# LoRa_RX.net
KiCad netlist of a schematic drawn in Altium Designer
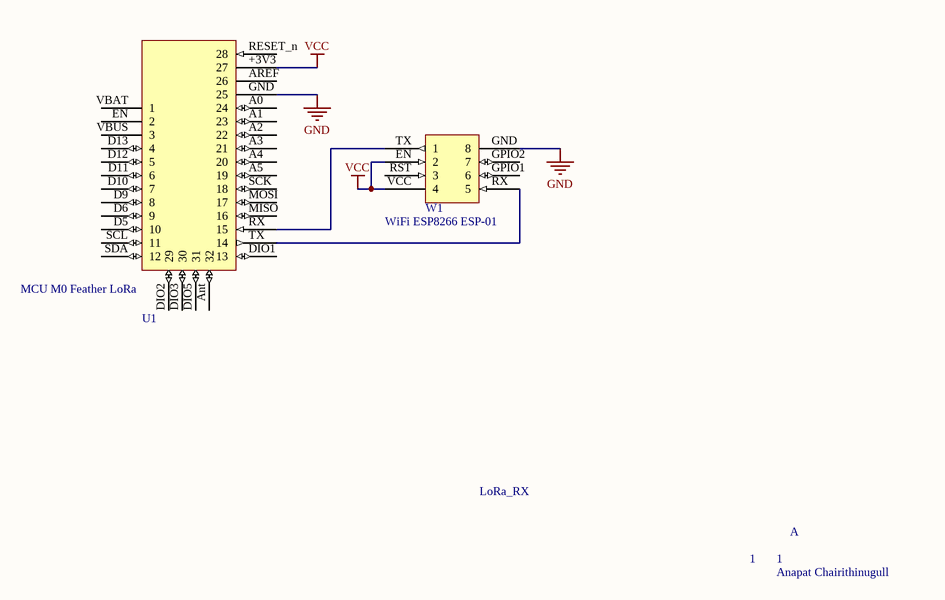
[diagram p0: LoRa_RX.SchDoc]

(export (version "E")
  (design (tool "Eeschema 10.0.6"))
  (components
    (comp (ref "U1") (value "MCU M0 Feather LoRa") (libsource (lib "Modules") (part "MCU M0 Feather LoRa")))
    (comp (ref "W1") (value "WiFi ESP8266 ESP-01") (libsource (lib "Modules") (part "WiFi ESP8266 ESP-01")))
  )
  (nets
    (net (code "1") (name "GND") (class "Default")
      (node (ref "U1") (pin "GND") (pinfunction "25_GND") (pintype "power_in"))
      (node (ref "W1") (pin "GND") (pinfunction "8_GND") (pintype "power_in"))
    )
    (net (code "2") (name "Net-(U1-14)") (class "Default")
      (node (ref "U1") (pin "TX") (pinfunction "14_TX") (pintype "output"))
      (node (ref "W1") (pin "RX") (pinfunction "5_RX") (pintype "input"))
    )
    (net (code "3") (name "Net-(U1-15)") (class "Default")
      (node (ref "U1") (pin "RX") (pinfunction "15_RX") (pintype "input"))
      (node (ref "W1") (pin "TX") (pinfunction "1_TX") (pintype "output"))
    )
    (net (code "4") (name "VCC") (class "Default")
      (node (ref "U1") (pin "+3V3") (pinfunction "27_+3V3") (pintype "power_in"))
      (node (ref "W1") (pin "EN") (pinfunction "2_EN") (pintype "input"))
      (node (ref "W1") (pin "VCC") (pinfunction "4_VCC") (pintype "power_in"))
    )
    (net (code "5") (name "unconnected-(U1-1-PadVBAT)") (class "Default")
      (node (ref "U1") (pin "VBAT") (pinfunction "1_VBAT") (pintype "power_in"))
    )
    (net (code "6") (name "unconnected-(U1-2-PadEN)") (class "Default")
      (node (ref "U1") (pin "EN") (pinfunction "2_EN") (pintype "power_in"))
    )
    (net (code "7") (name "unconnected-(U1-3-PadVBUS)") (class "Default")
      (node (ref "U1") (pin "VBUS") (pinfunction "3_VBUS") (pintype "power_in"))
    )
    (net (code "8") (name "unconnected-(U1-4-PadD13)") (class "Default")
      (node (ref "U1") (pin "D13") (pinfunction "4_D13") (pintype "bidirectional"))
    )
    (net (code "9") (name "unconnected-(U1-5-PadD12)") (class "Default")
      (node (ref "U1") (pin "D12") (pinfunction "5_D12") (pintype "bidirectional"))
    )
    (net (code "10") (name "unconnected-(U1-6-PadD11)") (class "Default")
      (node (ref "U1") (pin "D11") (pinfunction "6_D11") (pintype "bidirectional"))
    )
    (net (code "11") (name "unconnected-(U1-7-PadD10)") (class "Default")
      (node (ref "U1") (pin "D10") (pinfunction "7_D10") (pintype "bidirectional"))
    )
    (net (code "12") (name "unconnected-(U1-8-PadD9)") (class "Default")
      (node (ref "U1") (pin "D9") (pinfunction "8_D9") (pintype "bidirectional"))
    )
    (net (code "13") (name "unconnected-(U1-9-PadD6)") (class "Default")
      (node (ref "U1") (pin "D6") (pinfunction "9_D6") (pintype "bidirectional"))
    )
    (net (code "14") (name "unconnected-(U1-10-PadD5)") (class "Default")
      (node (ref "U1") (pin "D5") (pinfunction "10_D5") (pintype "bidirectional"))
    )
    (net (code "15") (name "unconnected-(U1-11-PadSCL)") (class "Default")
      (node (ref "U1") (pin "SCL") (pinfunction "11_SCL") (pintype "bidirectional"))
    )
    (net (code "16") (name "unconnected-(U1-12-PadSDA)") (class "Default")
      (node (ref "U1") (pin "SDA") (pinfunction "12_SDA") (pintype "bidirectional"))
    )
    (net (code "17") (name "unconnected-(U1-13-PadDIO1)") (class "Default")
      (node (ref "U1") (pin "DIO1") (pinfunction "13_DIO1") (pintype "bidirectional"))
    )
    (net (code "18") (name "unconnected-(U1-16-PadMISO)") (class "Default")
      (node (ref "U1") (pin "MISO") (pinfunction "16_MISO") (pintype "bidirectional"))
    )
    (net (code "19") (name "unconnected-(U1-17-PadMOSI)") (class "Default")
      (node (ref "U1") (pin "MOSI") (pinfunction "17_MOSI") (pintype "bidirectional"))
    )
    (net (code "20") (name "unconnected-(U1-18-PadSCK)") (class "Default")
      (node (ref "U1") (pin "SCK") (pinfunction "18_SCK") (pintype "bidirectional"))
    )
    (net (code "21") (name "unconnected-(U1-19-PadA5)") (class "Default")
      (node (ref "U1") (pin "A5") (pinfunction "19_A5") (pintype "bidirectional"))
    )
    (net (code "22") (name "unconnected-(U1-20-PadA4)") (class "Default")
      (node (ref "U1") (pin "A4") (pinfunction "20_A4") (pintype "bidirectional"))
    )
    (net (code "23") (name "unconnected-(U1-21-PadA3)") (class "Default")
      (node (ref "U1") (pin "A3") (pinfunction "21_A3") (pintype "bidirectional"))
    )
    (net (code "24") (name "unconnected-(U1-22-PadA2)") (class "Default")
      (node (ref "U1") (pin "A2") (pinfunction "22_A2") (pintype "bidirectional"))
    )
    (net (code "25") (name "unconnected-(U1-23-PadA1)") (class "Default")
      (node (ref "U1") (pin "A1") (pinfunction "23_A1") (pintype "bidirectional"))
    )
    (net (code "26") (name "unconnected-(U1-24-PadA0)") (class "Default")
      (node (ref "U1") (pin "A0") (pinfunction "24_A0") (pintype "bidirectional"))
    )
    (net (code "27") (name "unconnected-(U1-26-PadAREF)") (class "Default")
      (node (ref "U1") (pin "AREF") (pinfunction "26_AREF") (pintype "power_in"))
    )
    (net (code "28") (name "unconnected-(U1-28-PadRESET_n)") (class "Default")
      (node (ref "U1") (pin "RESET_n") (pinfunction "28_RESET_n") (pintype "input"))
    )
    (net (code "29") (name "unconnected-(U1-29-PadDIO2)") (class "Default")
      (node (ref "U1") (pin "DIO2") (pinfunction "29_DIO2") (pintype "bidirectional"))
    )
    (net (code "30") (name "unconnected-(U1-30-PadDIO3)") (class "Default")
      (node (ref "U1") (pin "DIO3") (pinfunction "30_DIO3") (pintype "bidirectional"))
    )
    (net (code "31") (name "unconnected-(U1-31-PadDIO5)") (class "Default")
      (node (ref "U1") (pin "DIO5") (pinfunction "31_DIO5") (pintype "bidirectional"))
    )
    (net (code "32") (name "unconnected-(U1-32-PadAnt)") (class "Default")
      (node (ref "U1") (pin "Ant") (pinfunction "32_Ant") (pintype "bidirectional"))
    )
    (net (code "33") (name "unconnected-(W1-3-PadRST)") (class "Default")
      (node (ref "W1") (pin "RST") (pinfunction "3_RST") (pintype "input"))
    )
    (net (code "34") (name "unconnected-(W1-6-PadGPIO1)") (class "Default")
      (node (ref "W1") (pin "GPIO1") (pinfunction "6_GPIO1") (pintype "bidirectional"))
    )
    (net (code "35") (name "unconnected-(W1-7-PadGPIO2)") (class "Default")
      (node (ref "W1") (pin "GPIO2") (pinfunction "7_GPIO2") (pintype "bidirectional"))
    )
  )
)
